# singlesided.net
KiCad netlist of a schematic drawn in EAGLE
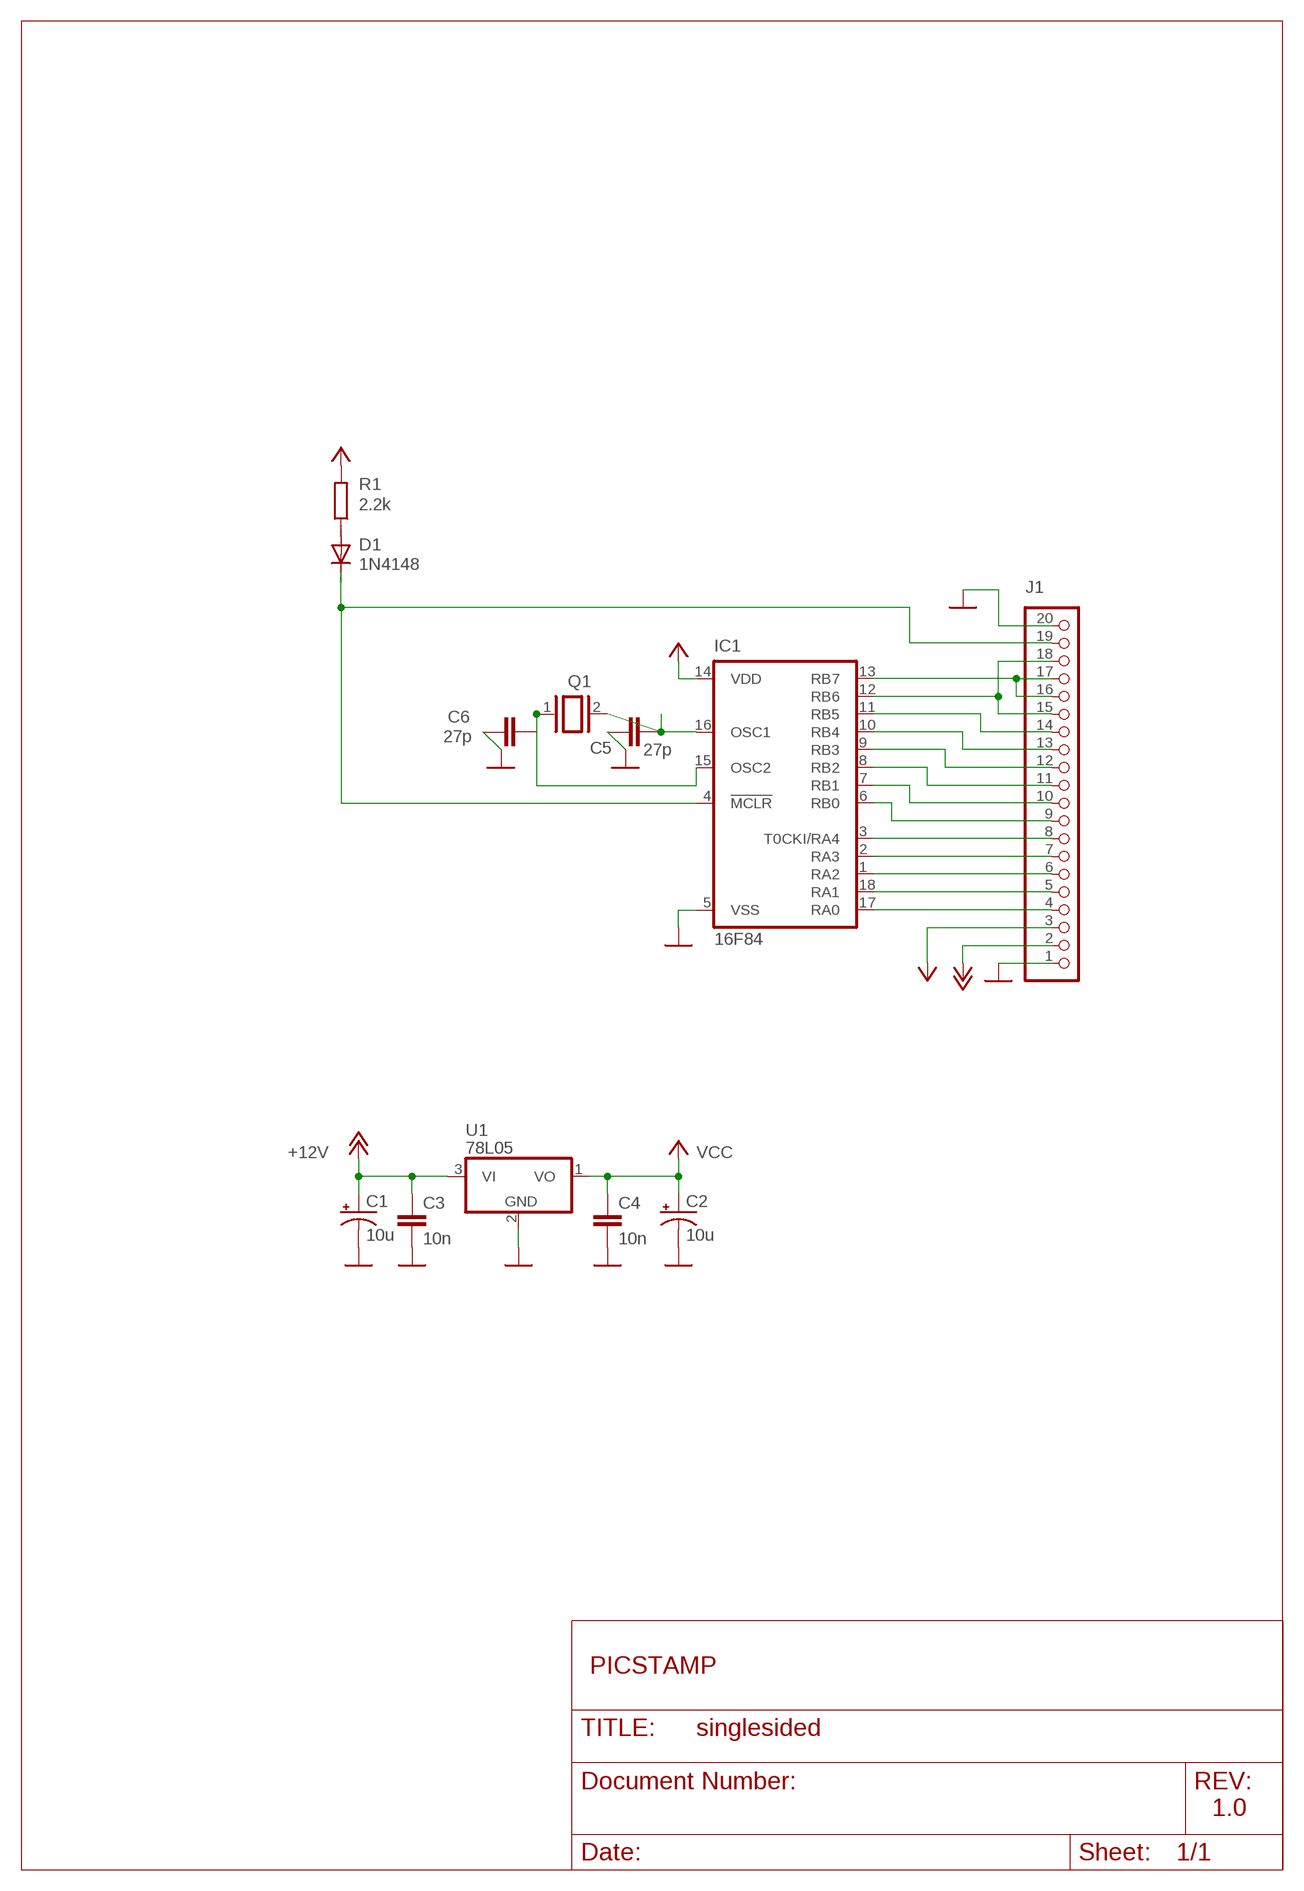
[diagram p0: schematic, sheet 1]

(export (version "E")
  (design (tool "Eeschema 10.0.6"))
  (components
    (comp (ref "C1")
      (value "10u")
      (footprint "eagle-import:E2,5-6")
      (libsource (lib "eagle-import") (part "CPOL-USE2.5-6"))
    )
    (comp (ref "C2")
      (value "10u")
      (footprint "eagle-import:E2,5-6")
      (libsource (lib "eagle-import") (part "CPOL-USE2.5-6"))
    )
    (comp (ref "C3")
      (value "10n")
      (footprint "eagle-import:C025-025X050")
      (libsource (lib "eagle-import") (part "C-EU025-025X050"))
    )
    (comp (ref "C4")
      (value "10n")
      (footprint "eagle-import:C025-025X050")
      (libsource (lib "eagle-import") (part "C-EU025-025X050"))
    )
    (comp (ref "C5")
      (value "27p")
      (footprint "eagle-import:C2.5-2")
      (libsource (lib "eagle-import") (part "C2.5/2"))
    )
    (comp (ref "C6")
      (value "27p")
      (footprint "eagle-import:C2.5-2")
      (libsource (lib "eagle-import") (part "C2.5/2"))
    )
    (comp (ref "D1")
      (value "1N4148")
      (footprint "eagle-import:DO35-10")
      (libsource (lib "eagle-import") (part "1N4148DO35-10"))
    )
    (comp (ref "IC1")
      (value "16F84")
      (footprint "eagle-import:DIL18")
      (fields (field (name "MF") "MICROCHIP") (field (name "MPN") "PIC16F84A-04I/P"))
      (libsource (lib "eagle-import") (part "PIC16F8P4A"))
    )
    (comp (ref "J1")
      (value "PINHD-1X20")
      (footprint "eagle-import:1X20")
      (libsource (lib "eagle-import") (part "PINHD-1X20"))
    )
    (comp (ref "Q1")
      (value "XTAL/S")
      (footprint "eagle-import:QS")
      (libsource (lib "eagle-import") (part "XTAL/S"))
    )
    (comp (ref "R1")
      (value "2.2k")
      (footprint "eagle-import:0207_10")
      (libsource (lib "eagle-import") (part "R-EU_0207/10"))
    )
    (comp (ref "U1")
      (value "78L05")
      (footprint "eagle-import:TO92")
      (libsource (lib "eagle-import") (part "78L05"))
    )
  )
  (nets
    (net (code "1") (name "+12V") (class "Default")
      (node (ref "C1") (pin "+") (pinfunction "+_+") (pintype "passive"))
      (node (ref "C3") (pin "1") (pinfunction "1_1") (pintype "passive"))
      (node (ref "J1") (pin "2") (pinfunction "2_2") (pintype "passive"))
      (node (ref "U1") (pin "3") (pinfunction "VI_3") (pintype "input"))
    )
    (net (code "2") (name "GND") (class "Default")
      (node (ref "C1") (pin "-") (pinfunction "-_-") (pintype "passive"))
      (node (ref "C2") (pin "-") (pinfunction "-_-") (pintype "passive"))
      (node (ref "C3") (pin "2") (pinfunction "2_2") (pintype "passive"))
      (node (ref "C4") (pin "2") (pinfunction "2_2") (pintype "passive"))
      (node (ref "C5") (pin "1") (pinfunction "1_1") (pintype "passive"))
      (node (ref "C6") (pin "1") (pinfunction "1_1") (pintype "passive"))
      (node (ref "IC1") (pin "5") (pinfunction "VSS_5") (pintype "power_in"))
      (node (ref "J1") (pin "1") (pinfunction "1_1") (pintype "passive"))
      (node (ref "J1") (pin "20") (pinfunction "20_20") (pintype "passive"))
      (node (ref "U1") (pin "2") (pinfunction "GND_2") (pintype "passive"))
    )
    (net (code "3") (name "Net-(D1-PadA)") (class "Default")
      (node (ref "D1") (pin "A") (pinfunction "A_A") (pintype "passive"))
      (node (ref "R1") (pin "1") (pinfunction "1_1") (pintype "passive"))
    )
    (net (code "4") (name "Net-(IC1-OSC1)") (class "Default")
      (node (ref "C5") (pin "2") (pinfunction "2_2") (pintype "passive"))
      (node (ref "IC1") (pin "16") (pinfunction "OSC1_16") (pintype "input"))
      (node (ref "Q1") (pin "2") (pinfunction "2_2") (pintype "passive"))
    )
    (net (code "5") (name "Net-(IC1-OSC2)") (class "Default")
      (node (ref "C6") (pin "2") (pinfunction "2_2") (pintype "passive"))
      (node (ref "IC1") (pin "15") (pinfunction "OSC2_15") (pintype "output"))
      (node (ref "Q1") (pin "1") (pinfunction "1_1") (pintype "passive"))
    )
    (net (code "6") (name "Net-(IC1-RA0)") (class "Default")
      (node (ref "IC1") (pin "17") (pinfunction "RA0_17") (pintype "bidirectional"))
      (node (ref "J1") (pin "4") (pinfunction "4_4") (pintype "passive"))
    )
    (net (code "7") (name "Net-(IC1-RA1)") (class "Default")
      (node (ref "IC1") (pin "18") (pinfunction "RA1_18") (pintype "bidirectional"))
      (node (ref "J1") (pin "5") (pinfunction "5_5") (pintype "passive"))
    )
    (net (code "8") (name "Net-(IC1-RA2)") (class "Default")
      (node (ref "IC1") (pin "1") (pinfunction "RA2_1") (pintype "bidirectional"))
      (node (ref "J1") (pin "6") (pinfunction "6_6") (pintype "passive"))
    )
    (net (code "9") (name "Net-(IC1-RA3)") (class "Default")
      (node (ref "IC1") (pin "2") (pinfunction "RA3_2") (pintype "bidirectional"))
      (node (ref "J1") (pin "7") (pinfunction "7_7") (pintype "passive"))
    )
    (net (code "10") (name "Net-(IC1-RB0)") (class "Default")
      (node (ref "IC1") (pin "6") (pinfunction "RB0_6") (pintype "bidirectional"))
      (node (ref "J1") (pin "9") (pinfunction "9_9") (pintype "passive"))
    )
    (net (code "11") (name "Net-(IC1-RB1)") (class "Default")
      (node (ref "IC1") (pin "7") (pinfunction "RB1_7") (pintype "bidirectional"))
      (node (ref "J1") (pin "10") (pinfunction "10_10") (pintype "passive"))
    )
    (net (code "12") (name "Net-(IC1-RB2)") (class "Default")
      (node (ref "IC1") (pin "8") (pinfunction "RB2_8") (pintype "bidirectional"))
      (node (ref "J1") (pin "11") (pinfunction "11_11") (pintype "passive"))
    )
    (net (code "13") (name "Net-(IC1-RB3)") (class "Default")
      (node (ref "IC1") (pin "9") (pinfunction "RB3_9") (pintype "bidirectional"))
      (node (ref "J1") (pin "12") (pinfunction "12_12") (pintype "passive"))
    )
    (net (code "14") (name "Net-(IC1-RB4)") (class "Default")
      (node (ref "IC1") (pin "10") (pinfunction "RB4_10") (pintype "bidirectional"))
      (node (ref "J1") (pin "13") (pinfunction "13_13") (pintype "passive"))
    )
    (net (code "15") (name "Net-(IC1-RB5)") (class "Default")
      (node (ref "IC1") (pin "11") (pinfunction "RB5_11") (pintype "bidirectional"))
      (node (ref "J1") (pin "14") (pinfunction "14_14") (pintype "passive"))
    )
    (net (code "16") (name "Net-(IC1-RB6)") (class "Default")
      (node (ref "IC1") (pin "12") (pinfunction "RB6_12") (pintype "bidirectional"))
      (node (ref "J1") (pin "15") (pinfunction "15_15") (pintype "passive"))
      (node (ref "J1") (pin "18") (pinfunction "18_18") (pintype "passive"))
    )
    (net (code "17") (name "Net-(IC1-RB7)") (class "Default")
      (node (ref "IC1") (pin "13") (pinfunction "RB7_13") (pintype "bidirectional"))
      (node (ref "J1") (pin "16") (pinfunction "16_16") (pintype "passive"))
      (node (ref "J1") (pin "17") (pinfunction "17_17") (pintype "passive"))
    )
    (net (code "18") (name "Net-(IC1-T0CKI{slash}RA4)") (class "Default")
      (node (ref "IC1") (pin "3") (pinfunction "T0CKI/RA4_3") (pintype "bidirectional"))
      (node (ref "J1") (pin "8") (pinfunction "8_8") (pintype "passive"))
    )
    (net (code "19") (name "Net-(IC1-~{MCLR})") (class "Default")
      (node (ref "D1") (pin "C") (pinfunction "C_C") (pintype "passive"))
      (node (ref "IC1") (pin "4") (pinfunction "~{MCLR}_4") (pintype "input"))
      (node (ref "J1") (pin "19") (pinfunction "19_19") (pintype "passive"))
    )
    (net (code "20") (name "VCC") (class "Default")
      (node (ref "C2") (pin "+") (pinfunction "+_+") (pintype "passive"))
      (node (ref "C4") (pin "1") (pinfunction "1_1") (pintype "passive"))
      (node (ref "IC1") (pin "14") (pinfunction "VDD_14") (pintype "power_in"))
      (node (ref "J1") (pin "3") (pinfunction "3_3") (pintype "passive"))
      (node (ref "R1") (pin "2") (pinfunction "2_2") (pintype "passive"))
      (node (ref "U1") (pin "1") (pinfunction "VO_1") (pintype "passive"))
    )
  )
)
